# teiler10e7V2.net
KiCad netlist of a schematic drawn in EAGLE
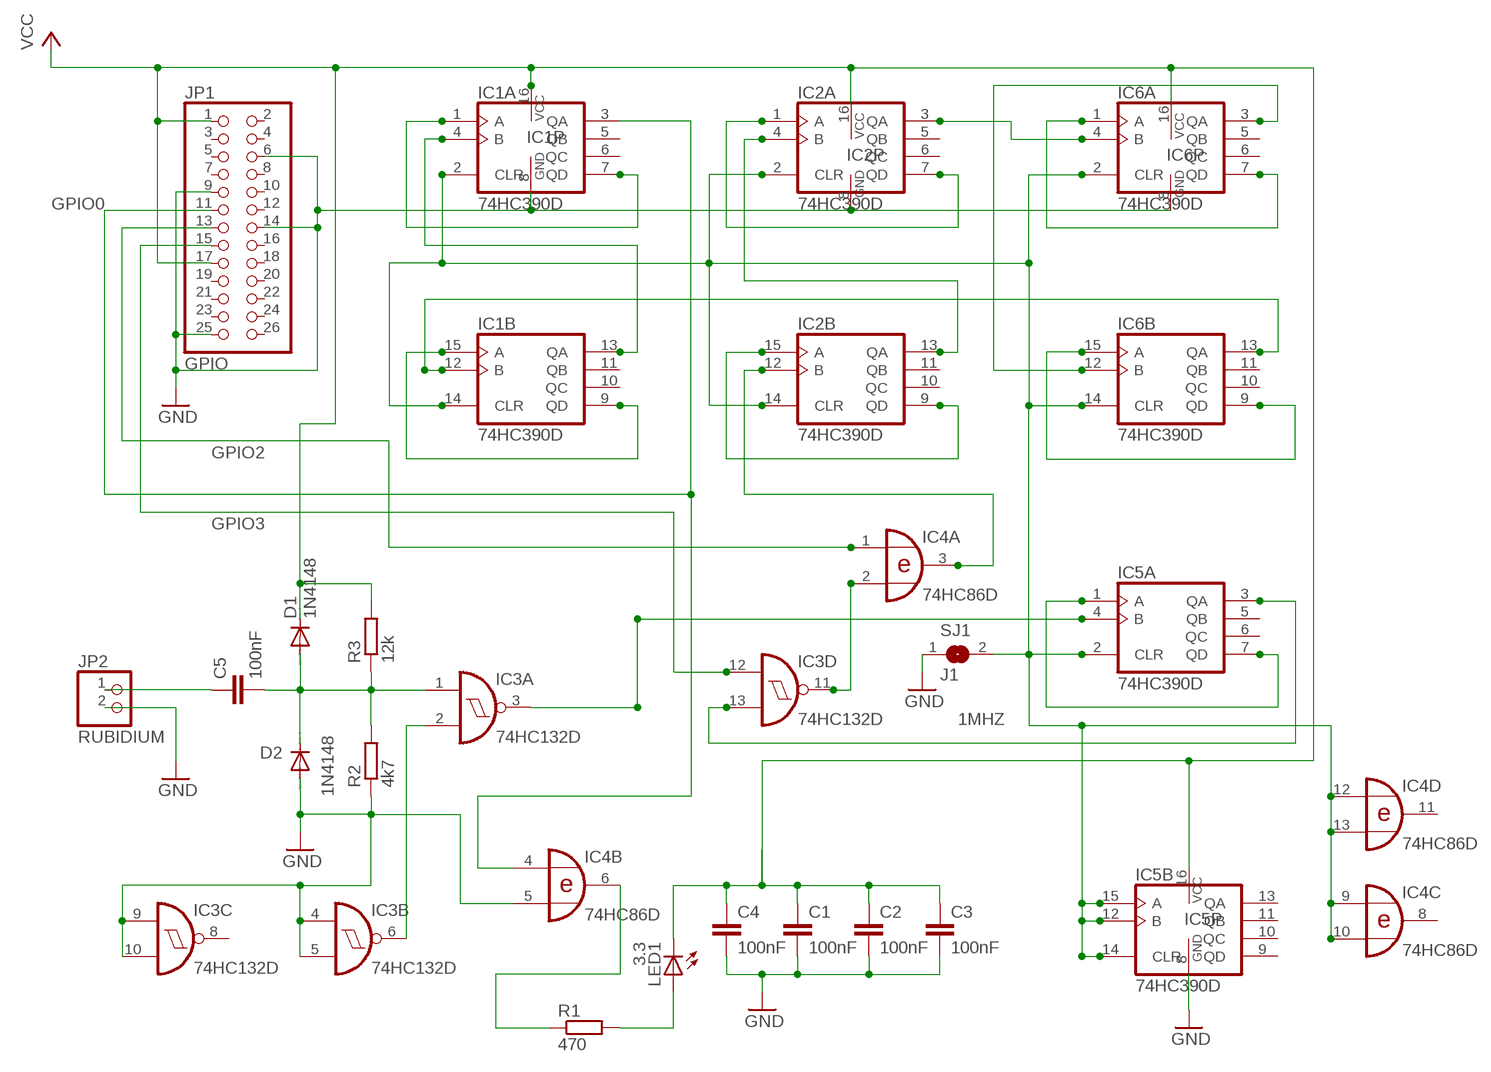
[diagram p0: schematic, sheet 1]

(export (version "E")
  (design (tool "Eeschema 10.0.6"))
  (components
    (comp (ref "C1")
      (value "100nF")
      (footprint "eagle-import:C025-025X050")
      (libsource (lib "eagle-import") (part "C-EU025-025X050"))
    )
    (comp (ref "C2")
      (value "100nF")
      (footprint "eagle-import:C025-025X050")
      (libsource (lib "eagle-import") (part "C-EU025-025X050"))
    )
    (comp (ref "C3")
      (value "100nF")
      (footprint "eagle-import:C025-025X050")
      (libsource (lib "eagle-import") (part "C-EU025-025X050"))
    )
    (comp (ref "C4")
      (value "100nF")
      (footprint "eagle-import:C025-025X050")
      (libsource (lib "eagle-import") (part "C-EU025-025X050"))
    )
    (comp (ref "C5")
      (value "100nF")
      (footprint "eagle-import:C025-025X050")
      (libsource (lib "eagle-import") (part "C-EU025-025X050"))
    )
    (comp (ref "D1")
      (value "1N4148")
      (footprint "eagle-import:DO35-7")
      (libsource (lib "eagle-import") (part "1N4148DO35-7"))
    )
    (comp (ref "D2")
      (value "1N4148")
      (footprint "eagle-import:DO35-7")
      (libsource (lib "eagle-import") (part "1N4148DO35-7"))
    )
    (comp (ref "IC1")
      (value "74HC390D")
      (footprint "eagle-import:SO16")
      (libsource (lib "eagle-import") (part "74390DHC"))
    )
    (comp (ref "IC2")
      (value "74HC390D")
      (footprint "eagle-import:SO16")
      (libsource (lib "eagle-import") (part "74390DHC"))
    )
    (comp (ref "IC3")
      (value "74HC132D")
      (footprint "eagle-import:SO14")
      (libsource (lib "eagle-import") (part "74132DHC"))
    )
    (comp (ref "IC4")
      (value "74HC86D")
      (footprint "eagle-import:SO14")
      (libsource (lib "eagle-import") (part "7486DHC"))
    )
    (comp (ref "IC5")
      (value "74HC390D")
      (footprint "eagle-import:SO16")
      (libsource (lib "eagle-import") (part "74390DHC"))
    )
    (comp (ref "IC6")
      (value "74HC390D")
      (footprint "eagle-import:SO16")
      (libsource (lib "eagle-import") (part "74390DHC"))
    )
    (comp (ref "JP1")
      (value "GPIO")
      (footprint "eagle-import:2X13")
      (libsource (lib "eagle-import") (part "PINHD-2X13"))
    )
    (comp (ref "JP2")
      (value "RUBIDIUM")
      (footprint "eagle-import:1X02_90")
      (libsource (lib "eagle-import") (part "PINHD-1X2/90"))
    )
    (comp (ref "LED1")
      (value "3.3")
      (footprint "eagle-import:LED3MM")
      (libsource (lib "eagle-import") (part "LED3MM"))
    )
    (comp (ref "R1")
      (value "470")
      (footprint "eagle-import:0207_10")
      (libsource (lib "eagle-import") (part "R-EU_0207/10"))
    )
    (comp (ref "R2")
      (value "4k7")
      (footprint "eagle-import:0207_10")
      (libsource (lib "eagle-import") (part "R-EU_0207/10"))
    )
    (comp (ref "R3")
      (value "12k")
      (footprint "eagle-import:0207_10")
      (libsource (lib "eagle-import") (part "R-EU_0207/10"))
    )
    (comp (ref "SJ1")
      (value "J1")
      (footprint "eagle-import:SJW")
      (libsource (lib "eagle-import") (part "SJW"))
    )
  )
  (nets
    (net (code "1") (name "/1MHZ") (class "Default")
      (node (ref "IC3") (pin "13") (pinfunction "I1_13") (pintype "input"))
      (node (ref "IC5") (pin "3") (pinfunction "QA_3") (pintype "output"))
    )
    (net (code "2") (name "/GPIO0") (class "Default")
      (node (ref "IC1") (pin "3") (pinfunction "QA_3") (pintype "output"))
      (node (ref "IC4") (pin "4") (pinfunction "I0_4") (pintype "input"))
      (node (ref "JP1") (pin "11") (pinfunction "11_11") (pintype "passive"))
    )
    (net (code "3") (name "/GPIO2") (class "Default")
      (node (ref "IC4") (pin "1") (pinfunction "I0_1") (pintype "input"))
      (node (ref "JP1") (pin "13") (pinfunction "13_13") (pintype "passive"))
    )
    (net (code "4") (name "/GPIO3") (class "Default")
      (node (ref "IC3") (pin "12") (pinfunction "I0_12") (pintype "input"))
      (node (ref "JP1") (pin "15") (pinfunction "15_15") (pintype "passive"))
    )
    (net (code "5") (name "GND") (class "Default")
      (node (ref "C1") (pin "2") (pinfunction "2_2") (pintype "passive"))
      (node (ref "C2") (pin "2") (pinfunction "2_2") (pintype "passive"))
      (node (ref "C3") (pin "2") (pinfunction "2_2") (pintype "passive"))
      (node (ref "C4") (pin "2") (pinfunction "2_2") (pintype "passive"))
      (node (ref "D2") (pin "A") (pinfunction "A_A") (pintype "passive"))
      (node (ref "IC1") (pin "8") (pinfunction "GND_8") (pintype "power_in"))
      (node (ref "IC2") (pin "8") (pinfunction "GND_8") (pintype "power_in"))
      (node (ref "IC3") (pin "10") (pinfunction "I1_10") (pintype "input"))
      (node (ref "IC3") (pin "4") (pinfunction "I0_4") (pintype "input"))
      (node (ref "IC3") (pin "5") (pinfunction "I1_5") (pintype "input"))
      (node (ref "IC3") (pin "9") (pinfunction "I0_9") (pintype "input"))
      (node (ref "IC4") (pin "5") (pinfunction "I1_5") (pintype "input"))
      (node (ref "IC5") (pin "8") (pinfunction "GND_8") (pintype "power_in"))
      (node (ref "IC6") (pin "8") (pinfunction "GND_8") (pintype "power_in"))
      (node (ref "JP1") (pin "14") (pinfunction "14_14") (pintype "passive"))
      (node (ref "JP1") (pin "25") (pinfunction "25_25") (pintype "passive"))
      (node (ref "JP1") (pin "6") (pinfunction "6_6") (pintype "passive"))
      (node (ref "JP1") (pin "9") (pinfunction "9_9") (pintype "passive"))
      (node (ref "JP2") (pin "2") (pinfunction "2_2") (pintype "passive"))
      (node (ref "R2") (pin "1") (pinfunction "1_1") (pintype "passive"))
      (node (ref "SJ1") (pin "1") (pinfunction "1_1") (pintype "passive"))
    )
    (net (code "6") (name "Net-(C5-Pad1)") (class "Default")
      (node (ref "C5") (pin "1") (pinfunction "1_1") (pintype "passive"))
      (node (ref "JP2") (pin "1") (pinfunction "1_1") (pintype "passive"))
    )
    (net (code "7") (name "Net-(IC1A-A)") (class "Default")
      (node (ref "IC1") (pin "1") (pinfunction "A_1") (pintype "input"))
      (node (ref "IC1") (pin "7") (pinfunction "QD_7") (pintype "output"))
    )
    (net (code "8") (name "Net-(IC1A-B)") (class "Default")
      (node (ref "IC1") (pin "13") (pinfunction "QA_13") (pintype "output"))
      (node (ref "IC1") (pin "4") (pinfunction "B_4") (pintype "input"))
    )
    (net (code "9") (name "Net-(IC1A-CLR)") (class "Default")
      (node (ref "IC1") (pin "14") (pinfunction "CLR_14") (pintype "input"))
      (node (ref "IC1") (pin "2") (pinfunction "CLR_2") (pintype "input"))
      (node (ref "IC2") (pin "14") (pinfunction "CLR_14") (pintype "input"))
      (node (ref "IC2") (pin "2") (pinfunction "CLR_2") (pintype "input"))
      (node (ref "IC4") (pin "10") (pinfunction "I1_10") (pintype "input"))
      (node (ref "IC4") (pin "12") (pinfunction "I0_12") (pintype "input"))
      (node (ref "IC4") (pin "13") (pinfunction "I1_13") (pintype "input"))
      (node (ref "IC4") (pin "9") (pinfunction "I0_9") (pintype "input"))
      (node (ref "IC5") (pin "12") (pinfunction "B_12") (pintype "input"))
      (node (ref "IC5") (pin "14") (pinfunction "CLR_14") (pintype "input"))
      (node (ref "IC5") (pin "15") (pinfunction "A_15") (pintype "input"))
      (node (ref "IC5") (pin "2") (pinfunction "CLR_2") (pintype "input"))
      (node (ref "IC6") (pin "14") (pinfunction "CLR_14") (pintype "input"))
      (node (ref "IC6") (pin "2") (pinfunction "CLR_2") (pintype "input"))
      (node (ref "SJ1") (pin "2") (pinfunction "2_2") (pintype "passive"))
    )
    (net (code "10") (name "Net-(IC1B-A)") (class "Default")
      (node (ref "IC1") (pin "15") (pinfunction "A_15") (pintype "input"))
      (node (ref "IC1") (pin "9") (pinfunction "QD_9") (pintype "output"))
    )
    (net (code "11") (name "Net-(IC1B-B)") (class "Default")
      (node (ref "IC1") (pin "12") (pinfunction "B_12") (pintype "input"))
      (node (ref "IC6") (pin "13") (pinfunction "QA_13") (pintype "output"))
    )
    (net (code "12") (name "Net-(IC2A-A)") (class "Default")
      (node (ref "IC2") (pin "1") (pinfunction "A_1") (pintype "input"))
      (node (ref "IC2") (pin "7") (pinfunction "QD_7") (pintype "output"))
    )
    (net (code "13") (name "Net-(IC2A-B)") (class "Default")
      (node (ref "IC2") (pin "13") (pinfunction "QA_13") (pintype "output"))
      (node (ref "IC2") (pin "4") (pinfunction "B_4") (pintype "input"))
    )
    (net (code "14") (name "Net-(IC2A-QA)") (class "Default")
      (node (ref "IC2") (pin "3") (pinfunction "QA_3") (pintype "output"))
      (node (ref "IC6") (pin "4") (pinfunction "B_4") (pintype "input"))
    )
    (net (code "15") (name "Net-(IC2B-A)") (class "Default")
      (node (ref "IC2") (pin "15") (pinfunction "A_15") (pintype "input"))
      (node (ref "IC2") (pin "9") (pinfunction "QD_9") (pintype "output"))
    )
    (net (code "16") (name "Net-(IC2B-B)") (class "Default")
      (node (ref "IC2") (pin "12") (pinfunction "B_12") (pintype "input"))
      (node (ref "IC4") (pin "3") (pinfunction "O_3") (pintype "output"))
    )
    (net (code "17") (name "Net-(IC3A-I0)") (class "Default")
      (node (ref "C5") (pin "2") (pinfunction "2_2") (pintype "passive"))
      (node (ref "D1") (pin "A") (pinfunction "A_A") (pintype "passive"))
      (node (ref "D2") (pin "C") (pinfunction "C_C") (pintype "passive"))
      (node (ref "IC3") (pin "1") (pinfunction "I0_1") (pintype "input"))
      (node (ref "R2") (pin "2") (pinfunction "2_2") (pintype "passive"))
      (node (ref "R3") (pin "1") (pinfunction "1_1") (pintype "passive"))
    )
    (net (code "18") (name "Net-(IC3A-I1)") (class "Default")
      (node (ref "IC3") (pin "2") (pinfunction "I1_2") (pintype "input"))
      (node (ref "IC3") (pin "6") (pinfunction "O_6") (pintype "output"))
    )
    (net (code "19") (name "Net-(IC3A-O)") (class "Default")
      (node (ref "IC3") (pin "3") (pinfunction "O_3") (pintype "output"))
      (node (ref "IC5") (pin "4") (pinfunction "B_4") (pintype "input"))
    )
    (net (code "20") (name "Net-(IC3D-O)") (class "Default")
      (node (ref "IC3") (pin "11") (pinfunction "O_11") (pintype "output"))
      (node (ref "IC4") (pin "2") (pinfunction "I1_2") (pintype "input"))
    )
    (net (code "21") (name "Net-(IC4B-O)") (class "Default")
      (node (ref "IC4") (pin "6") (pinfunction "O_6") (pintype "output"))
      (node (ref "R1") (pin "1") (pinfunction "1_1") (pintype "passive"))
    )
    (net (code "22") (name "Net-(IC5A-A)") (class "Default")
      (node (ref "IC5") (pin "1") (pinfunction "A_1") (pintype "input"))
      (node (ref "IC5") (pin "7") (pinfunction "QD_7") (pintype "output"))
    )
    (net (code "23") (name "Net-(IC6A-A)") (class "Default")
      (node (ref "IC6") (pin "1") (pinfunction "A_1") (pintype "input"))
      (node (ref "IC6") (pin "7") (pinfunction "QD_7") (pintype "output"))
    )
    (net (code "24") (name "Net-(IC6A-QA)") (class "Default")
      (node (ref "IC6") (pin "12") (pinfunction "B_12") (pintype "input"))
      (node (ref "IC6") (pin "3") (pinfunction "QA_3") (pintype "output"))
    )
    (net (code "25") (name "Net-(IC6B-A)") (class "Default")
      (node (ref "IC6") (pin "15") (pinfunction "A_15") (pintype "input"))
      (node (ref "IC6") (pin "9") (pinfunction "QD_9") (pintype "output"))
    )
    (net (code "26") (name "Net-(LED1-PadA)") (class "Default")
      (node (ref "LED1") (pin "A") (pinfunction "A_A") (pintype "passive"))
      (node (ref "R1") (pin "2") (pinfunction "2_2") (pintype "passive"))
    )
    (net (code "27") (name "VCC") (class "Default")
      (node (ref "C1") (pin "1") (pinfunction "1_1") (pintype "passive"))
      (node (ref "C2") (pin "1") (pinfunction "1_1") (pintype "passive"))
      (node (ref "C3") (pin "1") (pinfunction "1_1") (pintype "passive"))
      (node (ref "C4") (pin "1") (pinfunction "1_1") (pintype "passive"))
      (node (ref "D1") (pin "C") (pinfunction "C_C") (pintype "passive"))
      (node (ref "IC1") (pin "16") (pinfunction "VCC_16") (pintype "power_in"))
      (node (ref "IC2") (pin "16") (pinfunction "VCC_16") (pintype "power_in"))
      (node (ref "IC5") (pin "16") (pinfunction "VCC_16") (pintype "power_in"))
      (node (ref "IC6") (pin "16") (pinfunction "VCC_16") (pintype "power_in"))
      (node (ref "JP1") (pin "1") (pinfunction "1_1") (pintype "passive"))
      (node (ref "JP1") (pin "17") (pinfunction "17_17") (pintype "passive"))
      (node (ref "LED1") (pin "K") (pinfunction "C_K") (pintype "passive"))
      (node (ref "R3") (pin "2") (pinfunction "2_2") (pintype "passive"))
    )
    (net (code "28") (name "unconnected-(IC1A-QB-Pad5)") (class "Default")
      (node (ref "IC1") (pin "5") (pinfunction "QB_5") (pintype "output"))
    )
    (net (code "29") (name "unconnected-(IC1A-QC-Pad6)") (class "Default")
      (node (ref "IC1") (pin "6") (pinfunction "QC_6") (pintype "output"))
    )
    (net (code "30") (name "unconnected-(IC1B-QB-Pad11)") (class "Default")
      (node (ref "IC1") (pin "11") (pinfunction "QB_11") (pintype "output"))
    )
    (net (code "31") (name "unconnected-(IC1B-QC-Pad10)") (class "Default")
      (node (ref "IC1") (pin "10") (pinfunction "QC_10") (pintype "output"))
    )
    (net (code "32") (name "unconnected-(IC2A-QB-Pad5)") (class "Default")
      (node (ref "IC2") (pin "5") (pinfunction "QB_5") (pintype "output"))
    )
    (net (code "33") (name "unconnected-(IC2A-QC-Pad6)") (class "Default")
      (node (ref "IC2") (pin "6") (pinfunction "QC_6") (pintype "output"))
    )
    (net (code "34") (name "unconnected-(IC2B-QB-Pad11)") (class "Default")
      (node (ref "IC2") (pin "11") (pinfunction "QB_11") (pintype "output"))
    )
    (net (code "35") (name "unconnected-(IC2B-QC-Pad10)") (class "Default")
      (node (ref "IC2") (pin "10") (pinfunction "QC_10") (pintype "output"))
    )
    (net (code "36") (name "unconnected-(IC3C-O-Pad8)") (class "Default")
      (node (ref "IC3") (pin "8") (pinfunction "O_8") (pintype "output"))
    )
    (net (code "37") (name "unconnected-(IC4C-O-Pad8)") (class "Default")
      (node (ref "IC4") (pin "8") (pinfunction "O_8") (pintype "output"))
    )
    (net (code "38") (name "unconnected-(IC4D-O-Pad11)") (class "Default")
      (node (ref "IC4") (pin "11") (pinfunction "O_11") (pintype "output"))
    )
    (net (code "39") (name "unconnected-(IC5A-QB-Pad5)") (class "Default")
      (node (ref "IC5") (pin "5") (pinfunction "QB_5") (pintype "output"))
    )
    (net (code "40") (name "unconnected-(IC5A-QC-Pad6)") (class "Default")
      (node (ref "IC5") (pin "6") (pinfunction "QC_6") (pintype "output"))
    )
    (net (code "41") (name "unconnected-(IC5B-QA-Pad13)") (class "Default")
      (node (ref "IC5") (pin "13") (pinfunction "QA_13") (pintype "output"))
    )
    (net (code "42") (name "unconnected-(IC5B-QB-Pad11)") (class "Default")
      (node (ref "IC5") (pin "11") (pinfunction "QB_11") (pintype "output"))
    )
    (net (code "43") (name "unconnected-(IC5B-QC-Pad10)") (class "Default")
      (node (ref "IC5") (pin "10") (pinfunction "QC_10") (pintype "output"))
    )
    (net (code "44") (name "unconnected-(IC5B-QD-Pad9)") (class "Default")
      (node (ref "IC5") (pin "9") (pinfunction "QD_9") (pintype "output"))
    )
    (net (code "45") (name "unconnected-(IC6A-QB-Pad5)") (class "Default")
      (node (ref "IC6") (pin "5") (pinfunction "QB_5") (pintype "output"))
    )
    (net (code "46") (name "unconnected-(IC6A-QC-Pad6)") (class "Default")
      (node (ref "IC6") (pin "6") (pinfunction "QC_6") (pintype "output"))
    )
    (net (code "47") (name "unconnected-(IC6B-QB-Pad11)") (class "Default")
      (node (ref "IC6") (pin "11") (pinfunction "QB_11") (pintype "output"))
    )
    (net (code "48") (name "unconnected-(IC6B-QC-Pad10)") (class "Default")
      (node (ref "IC6") (pin "10") (pinfunction "QC_10") (pintype "output"))
    )
    (net (code "49") (name "unconnected-(JP1-Pad2)") (class "Default")
      (node (ref "JP1") (pin "2") (pinfunction "2_2") (pintype "passive"))
    )
    (net (code "50") (name "unconnected-(JP1-Pad3)") (class "Default")
      (node (ref "JP1") (pin "3") (pinfunction "3_3") (pintype "passive"))
    )
    (net (code "51") (name "unconnected-(JP1-Pad4)") (class "Default")
      (node (ref "JP1") (pin "4") (pinfunction "4_4") (pintype "passive"))
    )
    (net (code "52") (name "unconnected-(JP1-Pad5)") (class "Default")
      (node (ref "JP1") (pin "5") (pinfunction "5_5") (pintype "passive"))
    )
    (net (code "53") (name "unconnected-(JP1-Pad7)") (class "Default")
      (node (ref "JP1") (pin "7") (pinfunction "7_7") (pintype "passive"))
    )
    (net (code "54") (name "unconnected-(JP1-Pad8)") (class "Default")
      (node (ref "JP1") (pin "8") (pinfunction "8_8") (pintype "passive"))
    )
    (net (code "55") (name "unconnected-(JP1-Pad10)") (class "Default")
      (node (ref "JP1") (pin "10") (pinfunction "10_10") (pintype "passive"))
    )
    (net (code "56") (name "unconnected-(JP1-Pad12)") (class "Default")
      (node (ref "JP1") (pin "12") (pinfunction "12_12") (pintype "passive"))
    )
    (net (code "57") (name "unconnected-(JP1-Pad16)") (class "Default")
      (node (ref "JP1") (pin "16") (pinfunction "16_16") (pintype "passive"))
    )
    (net (code "58") (name "unconnected-(JP1-Pad18)") (class "Default")
      (node (ref "JP1") (pin "18") (pinfunction "18_18") (pintype "passive"))
    )
    (net (code "59") (name "unconnected-(JP1-Pad19)") (class "Default")
      (node (ref "JP1") (pin "19") (pinfunction "19_19") (pintype "passive"))
    )
    (net (code "60") (name "unconnected-(JP1-Pad20)") (class "Default")
      (node (ref "JP1") (pin "20") (pinfunction "20_20") (pintype "passive"))
    )
    (net (code "61") (name "unconnected-(JP1-Pad21)") (class "Default")
      (node (ref "JP1") (pin "21") (pinfunction "21_21") (pintype "passive"))
    )
    (net (code "62") (name "unconnected-(JP1-Pad22)") (class "Default")
      (node (ref "JP1") (pin "22") (pinfunction "22_22") (pintype "passive"))
    )
    (net (code "63") (name "unconnected-(JP1-Pad23)") (class "Default")
      (node (ref "JP1") (pin "23") (pinfunction "23_23") (pintype "passive"))
    )
    (net (code "64") (name "unconnected-(JP1-Pad24)") (class "Default")
      (node (ref "JP1") (pin "24") (pinfunction "24_24") (pintype "passive"))
    )
    (net (code "65") (name "unconnected-(JP1-Pad26)") (class "Default")
      (node (ref "JP1") (pin "26") (pinfunction "26_26") (pintype "passive"))
    )
  )
)
